# 74lvc_ring_osc.net
KiCad netlist of a schematic drawn in EAGLE
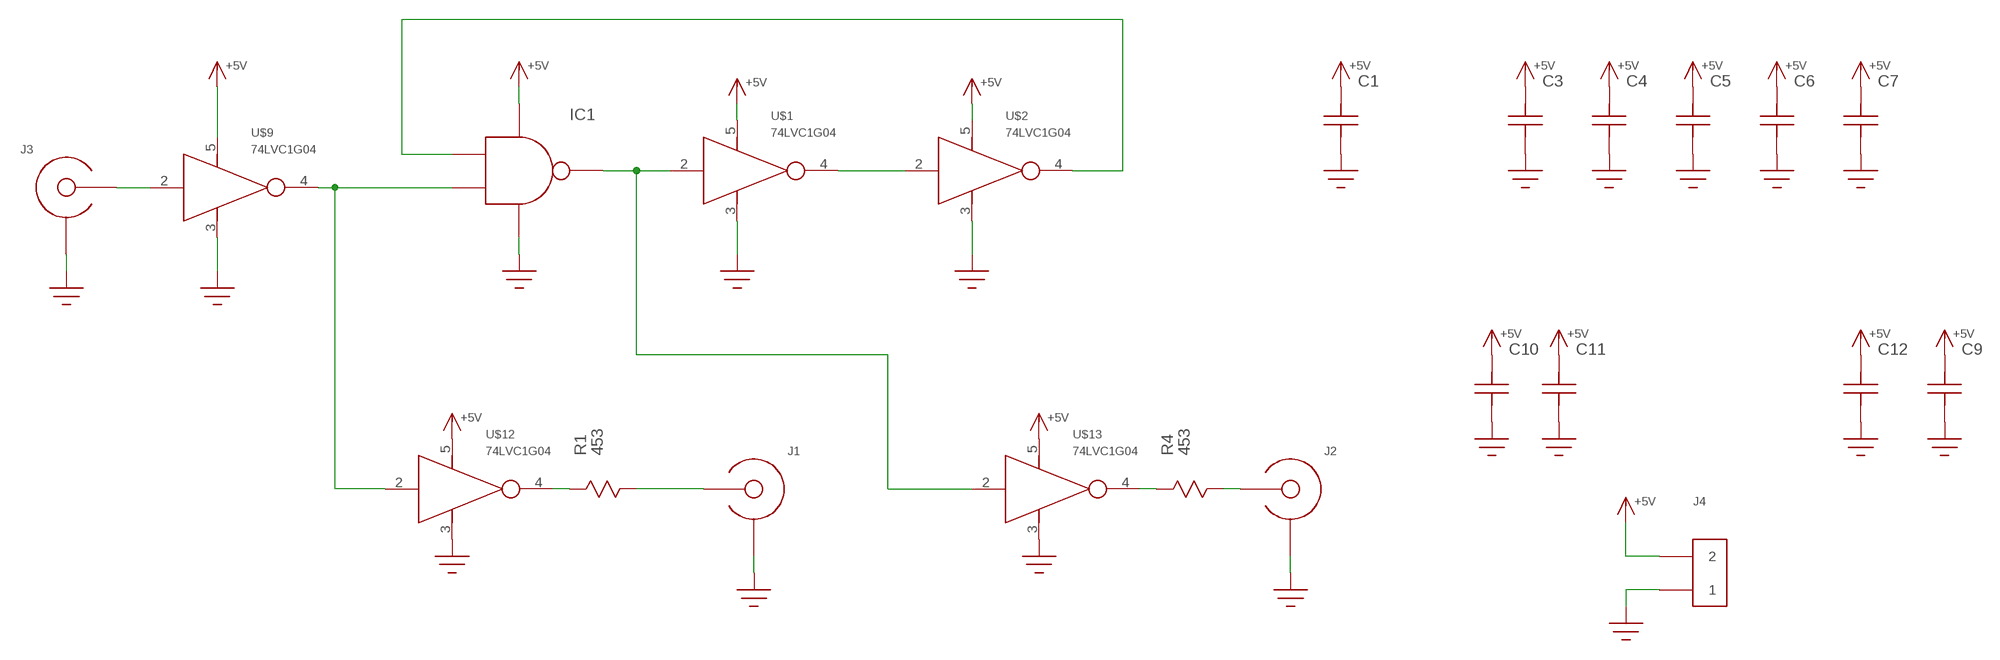
[diagram p0: schematic, sheet 1]

(export (version "E")
  (design (tool "Eeschema 10.0.6"))
  (components
    (comp (ref "C1")
      (value "C0603")
      (footprint "eagle-import:C0603")
      (libsource (lib "eagle-import") (part "C0603"))
    )
    (comp (ref "C3")
      (value "C0603")
      (footprint "eagle-import:C0603")
      (libsource (lib "eagle-import") (part "C0603"))
    )
    (comp (ref "C4")
      (value "C0603")
      (footprint "eagle-import:C0603")
      (libsource (lib "eagle-import") (part "C0603"))
    )
    (comp (ref "C5")
      (value "C0603")
      (footprint "eagle-import:C0603")
      (libsource (lib "eagle-import") (part "C0603"))
    )
    (comp (ref "C6")
      (value "C0603")
      (footprint "eagle-import:C0603")
      (libsource (lib "eagle-import") (part "C0603"))
    )
    (comp (ref "C7")
      (value "C0603")
      (footprint "eagle-import:C0603")
      (libsource (lib "eagle-import") (part "C0603"))
    )
    (comp (ref "C9")
      (value "C1206")
      (footprint "eagle-import:1206")
      (libsource (lib "eagle-import") (part "C1206"))
    )
    (comp (ref "C10")
      (value "C0805")
      (footprint "eagle-import:0805")
      (libsource (lib "eagle-import") (part "C0805"))
    )
    (comp (ref "C11")
      (value "C0805")
      (footprint "eagle-import:0805")
      (libsource (lib "eagle-import") (part "C0805"))
    )
    (comp (ref "C12")
      (value "C1206")
      (footprint "eagle-import:1206")
      (libsource (lib "eagle-import") (part "C1206"))
    )
    (comp (ref "IC1")
      (value "74LVC1G00")
      (footprint "eagle-import:SOT23-5")
      (libsource (lib "eagle-import") (part "74LVC1G00"))
    )
    (comp (ref "J1")
      (value "EDGE_LAUNCH_JACK")
      (footprint "eagle-import:EDGE_LAUNCH_RF_CON")
      (libsource (lib "eagle-import") (part "EDGE_LAUNCH_JACK"))
    )
    (comp (ref "J2")
      (value "EDGE_LAUNCH_JACK")
      (footprint "eagle-import:EDGE_LAUNCH_RF_CON")
      (libsource (lib "eagle-import") (part "EDGE_LAUNCH_JACK"))
    )
    (comp (ref "J3")
      (value "EDGE_LAUNCH_JACK")
      (footprint "eagle-import:EDGE_LAUNCH_RF_CON")
      (libsource (lib "eagle-import") (part "EDGE_LAUNCH_JACK"))
    )
    (comp (ref "J4")
      (value "HEADER_2PIN")
      (footprint "eagle-import:HEADER_2PIN")
      (libsource (lib "eagle-import") (part "HEADER_2PIN"))
    )
    (comp (ref "R1")
      (value "453")
      (footprint "eagle-import:R0805")
      (libsource (lib "eagle-import") (part "R0805"))
    )
    (comp (ref "R4")
      (value "453")
      (footprint "eagle-import:R0805")
      (libsource (lib "eagle-import") (part "R0805"))
    )
    (comp (ref "U$1")
      (value "74LVC1G04")
      (footprint "eagle-import:SOT23-5")
      (libsource (lib "eagle-import") (part "74LVC1G04"))
    )
    (comp (ref "U$2")
      (value "74LVC1G04")
      (footprint "eagle-import:SOT23-5")
      (libsource (lib "eagle-import") (part "74LVC1G04"))
    )
    (comp (ref "U$9")
      (value "74LVC1G04")
      (footprint "eagle-import:SOT23-5")
      (libsource (lib "eagle-import") (part "74LVC1G04"))
    )
    (comp (ref "U$12")
      (value "74LVC1G04")
      (footprint "eagle-import:SOT23-5")
      (libsource (lib "eagle-import") (part "74LVC1G04"))
    )
    (comp (ref "U$13")
      (value "74LVC1G04")
      (footprint "eagle-import:SOT23-5")
      (libsource (lib "eagle-import") (part "74LVC1G04"))
    )
  )
  (nets
    (net (code "1") (name "+5V") (class "Default")
      (node (ref "C1") (pin "P$2") (pinfunction "P$2_P$2") (pintype "bidirectional"))
      (node (ref "C10") (pin "P$2") (pinfunction "P$2_P$2") (pintype "bidirectional"))
      (node (ref "C11") (pin "P$2") (pinfunction "P$2_P$2") (pintype "bidirectional"))
      (node (ref "C12") (pin "P$2") (pinfunction "P$2_P$2") (pintype "bidirectional"))
      (node (ref "C3") (pin "P$2") (pinfunction "P$2_P$2") (pintype "bidirectional"))
      (node (ref "C4") (pin "P$2") (pinfunction "P$2_P$2") (pintype "bidirectional"))
      (node (ref "C5") (pin "P$2") (pinfunction "P$2_P$2") (pintype "bidirectional"))
      (node (ref "C6") (pin "P$2") (pinfunction "P$2_P$2") (pintype "bidirectional"))
      (node (ref "C7") (pin "P$2") (pinfunction "P$2_P$2") (pintype "bidirectional"))
      (node (ref "C9") (pin "P$2") (pinfunction "P$2_P$2") (pintype "bidirectional"))
      (node (ref "IC1") (pin "5") (pinfunction "VCC_5") (pintype "bidirectional"))
      (node (ref "J4") (pin "2") (pinfunction "2_2") (pintype "bidirectional"))
      (node (ref "U$1") (pin "5") (pinfunction "VCC_5") (pintype "bidirectional"))
      (node (ref "U$12") (pin "5") (pinfunction "VCC_5") (pintype "bidirectional"))
      (node (ref "U$13") (pin "5") (pinfunction "VCC_5") (pintype "bidirectional"))
      (node (ref "U$2") (pin "5") (pinfunction "VCC_5") (pintype "bidirectional"))
      (node (ref "U$9") (pin "5") (pinfunction "VCC_5") (pintype "bidirectional"))
    )
    (net (code "2") (name "GND") (class "Default")
      (node (ref "C1") (pin "P$1") (pinfunction "P$1_P$1") (pintype "bidirectional"))
      (node (ref "C10") (pin "P$1") (pinfunction "P$1_P$1") (pintype "bidirectional"))
      (node (ref "C11") (pin "P$1") (pinfunction "P$1_P$1") (pintype "bidirectional"))
      (node (ref "C12") (pin "P$1") (pinfunction "P$1_P$1") (pintype "bidirectional"))
      (node (ref "C3") (pin "P$1") (pinfunction "P$1_P$1") (pintype "bidirectional"))
      (node (ref "C4") (pin "P$1") (pinfunction "P$1_P$1") (pintype "bidirectional"))
      (node (ref "C5") (pin "P$1") (pinfunction "P$1_P$1") (pintype "bidirectional"))
      (node (ref "C6") (pin "P$1") (pinfunction "P$1_P$1") (pintype "bidirectional"))
      (node (ref "C7") (pin "P$1") (pinfunction "P$1_P$1") (pintype "bidirectional"))
      (node (ref "C9") (pin "P$1") (pinfunction "P$1_P$1") (pintype "bidirectional"))
      (node (ref "IC1") (pin "3") (pinfunction "GND_3") (pintype "bidirectional"))
      (node (ref "J1") (pin "GND@1") (pinfunction "SHIELD_GND@1") (pintype "bidirectional"))
      (node (ref "J1") (pin "GND@10") (pinfunction "SHIELD_GND@10") (pintype "bidirectional"))
      (node (ref "J1") (pin "GND@11") (pinfunction "SHIELD_GND@11") (pintype "bidirectional"))
      (node (ref "J1") (pin "GND@12") (pinfunction "SHIELD_GND@12") (pintype "bidirectional"))
      (node (ref "J1") (pin "GND@2") (pinfunction "SHIELD_GND@2") (pintype "bidirectional"))
      (node (ref "J1") (pin "GND@3") (pinfunction "SHIELD_GND@3") (pintype "bidirectional"))
      (node (ref "J1") (pin "GND@4") (pinfunction "SHIELD_GND@4") (pintype "bidirectional"))
      (node (ref "J1") (pin "GND@5") (pinfunction "SHIELD_GND@5") (pintype "bidirectional"))
      (node (ref "J1") (pin "GND@6") (pinfunction "SHIELD_GND@6") (pintype "bidirectional"))
      (node (ref "J1") (pin "GND@7") (pinfunction "SHIELD_GND@7") (pintype "bidirectional"))
      (node (ref "J1") (pin "GND@8") (pinfunction "SHIELD_GND@8") (pintype "bidirectional"))
      (node (ref "J1") (pin "GND@9") (pinfunction "SHIELD_GND@9") (pintype "bidirectional"))
      (node (ref "J1") (pin "SHIELD@1") (pinfunction "SHIELD_SHIELD@1") (pintype "bidirectional"))
      (node (ref "J1") (pin "SHIELD@2") (pinfunction "SHIELD_SHIELD@2") (pintype "bidirectional"))
      (node (ref "J2") (pin "GND@1") (pinfunction "SHIELD_GND@1") (pintype "bidirectional"))
      (node (ref "J2") (pin "GND@10") (pinfunction "SHIELD_GND@10") (pintype "bidirectional"))
      (node (ref "J2") (pin "GND@11") (pinfunction "SHIELD_GND@11") (pintype "bidirectional"))
      (node (ref "J2") (pin "GND@12") (pinfunction "SHIELD_GND@12") (pintype "bidirectional"))
      (node (ref "J2") (pin "GND@2") (pinfunction "SHIELD_GND@2") (pintype "bidirectional"))
      (node (ref "J2") (pin "GND@3") (pinfunction "SHIELD_GND@3") (pintype "bidirectional"))
      (node (ref "J2") (pin "GND@4") (pinfunction "SHIELD_GND@4") (pintype "bidirectional"))
      (node (ref "J2") (pin "GND@5") (pinfunction "SHIELD_GND@5") (pintype "bidirectional"))
      (node (ref "J2") (pin "GND@6") (pinfunction "SHIELD_GND@6") (pintype "bidirectional"))
      (node (ref "J2") (pin "GND@7") (pinfunction "SHIELD_GND@7") (pintype "bidirectional"))
      (node (ref "J2") (pin "GND@8") (pinfunction "SHIELD_GND@8") (pintype "bidirectional"))
      (node (ref "J2") (pin "GND@9") (pinfunction "SHIELD_GND@9") (pintype "bidirectional"))
      (node (ref "J2") (pin "SHIELD@1") (pinfunction "SHIELD_SHIELD@1") (pintype "bidirectional"))
      (node (ref "J2") (pin "SHIELD@2") (pinfunction "SHIELD_SHIELD@2") (pintype "bidirectional"))
      (node (ref "J3") (pin "GND@1") (pinfunction "SHIELD_GND@1") (pintype "bidirectional"))
      (node (ref "J3") (pin "GND@10") (pinfunction "SHIELD_GND@10") (pintype "bidirectional"))
      (node (ref "J3") (pin "GND@11") (pinfunction "SHIELD_GND@11") (pintype "bidirectional"))
      (node (ref "J3") (pin "GND@12") (pinfunction "SHIELD_GND@12") (pintype "bidirectional"))
      (node (ref "J3") (pin "GND@2") (pinfunction "SHIELD_GND@2") (pintype "bidirectional"))
      (node (ref "J3") (pin "GND@3") (pinfunction "SHIELD_GND@3") (pintype "bidirectional"))
      (node (ref "J3") (pin "GND@4") (pinfunction "SHIELD_GND@4") (pintype "bidirectional"))
      (node (ref "J3") (pin "GND@5") (pinfunction "SHIELD_GND@5") (pintype "bidirectional"))
      (node (ref "J3") (pin "GND@6") (pinfunction "SHIELD_GND@6") (pintype "bidirectional"))
      (node (ref "J3") (pin "GND@7") (pinfunction "SHIELD_GND@7") (pintype "bidirectional"))
      (node (ref "J3") (pin "GND@8") (pinfunction "SHIELD_GND@8") (pintype "bidirectional"))
      (node (ref "J3") (pin "GND@9") (pinfunction "SHIELD_GND@9") (pintype "bidirectional"))
      (node (ref "J3") (pin "SHIELD@1") (pinfunction "SHIELD_SHIELD@1") (pintype "bidirectional"))
      (node (ref "J3") (pin "SHIELD@2") (pinfunction "SHIELD_SHIELD@2") (pintype "bidirectional"))
      (node (ref "J4") (pin "1") (pinfunction "1_1") (pintype "bidirectional"))
      (node (ref "U$1") (pin "3") (pinfunction "GND_3") (pintype "bidirectional"))
      (node (ref "U$12") (pin "3") (pinfunction "GND_3") (pintype "bidirectional"))
      (node (ref "U$13") (pin "3") (pinfunction "GND_3") (pintype "bidirectional"))
      (node (ref "U$2") (pin "3") (pinfunction "GND_3") (pintype "bidirectional"))
      (node (ref "U$9") (pin "3") (pinfunction "GND_3") (pintype "bidirectional"))
    )
    (net (code "3") (name "Net-(IC1-A)") (class "Default")
      (node (ref "IC1") (pin "2") (pinfunction "A_2") (pintype "bidirectional"))
      (node (ref "U$2") (pin "4") (pinfunction "OUT_4") (pintype "bidirectional"))
    )
    (net (code "4") (name "Net-(IC1-B)") (class "Default")
      (node (ref "IC1") (pin "1") (pinfunction "B_1") (pintype "bidirectional"))
      (node (ref "U$12") (pin "2") (pinfunction "IN_2") (pintype "bidirectional"))
      (node (ref "U$9") (pin "4") (pinfunction "OUT_4") (pintype "bidirectional"))
    )
    (net (code "5") (name "Net-(IC1-Y)") (class "Default")
      (node (ref "IC1") (pin "4") (pinfunction "Y_4") (pintype "bidirectional"))
      (node (ref "U$1") (pin "2") (pinfunction "IN_2") (pintype "bidirectional"))
      (node (ref "U$13") (pin "2") (pinfunction "IN_2") (pintype "bidirectional"))
    )
    (net (code "6") (name "Net-(R1-P$3)") (class "Default")
      (node (ref "R1") (pin "P$1") (pinfunction "P$3_P$1") (pintype "bidirectional"))
      (node (ref "U$12") (pin "4") (pinfunction "OUT_4") (pintype "bidirectional"))
    )
    (net (code "7") (name "Net-(R1-P$4)") (class "Default")
      (node (ref "J1") (pin "CENTER") (pinfunction "CENTER_CENTER") (pintype "bidirectional"))
      (node (ref "R1") (pin "P$2") (pinfunction "P$4_P$2") (pintype "bidirectional"))
    )
    (net (code "8") (name "Net-(R4-P$3)") (class "Default")
      (node (ref "R4") (pin "P$1") (pinfunction "P$3_P$1") (pintype "bidirectional"))
      (node (ref "U$13") (pin "4") (pinfunction "OUT_4") (pintype "bidirectional"))
    )
    (net (code "9") (name "Net-(R4-P$4)") (class "Default")
      (node (ref "J2") (pin "CENTER") (pinfunction "CENTER_CENTER") (pintype "bidirectional"))
      (node (ref "R4") (pin "P$2") (pinfunction "P$4_P$2") (pintype "bidirectional"))
    )
    (net (code "10") (name "Net-(U$1-OUT)") (class "Default")
      (node (ref "U$1") (pin "4") (pinfunction "OUT_4") (pintype "bidirectional"))
      (node (ref "U$2") (pin "2") (pinfunction "IN_2") (pintype "bidirectional"))
    )
    (net (code "11") (name "Net-(U$9-IN)") (class "Default")
      (node (ref "J3") (pin "CENTER") (pinfunction "CENTER_CENTER") (pintype "bidirectional"))
      (node (ref "U$9") (pin "2") (pinfunction "IN_2") (pintype "bidirectional"))
    )
  )
)
